# MB1066.net
KiCad netlist of a schematic drawn in Altium Designer
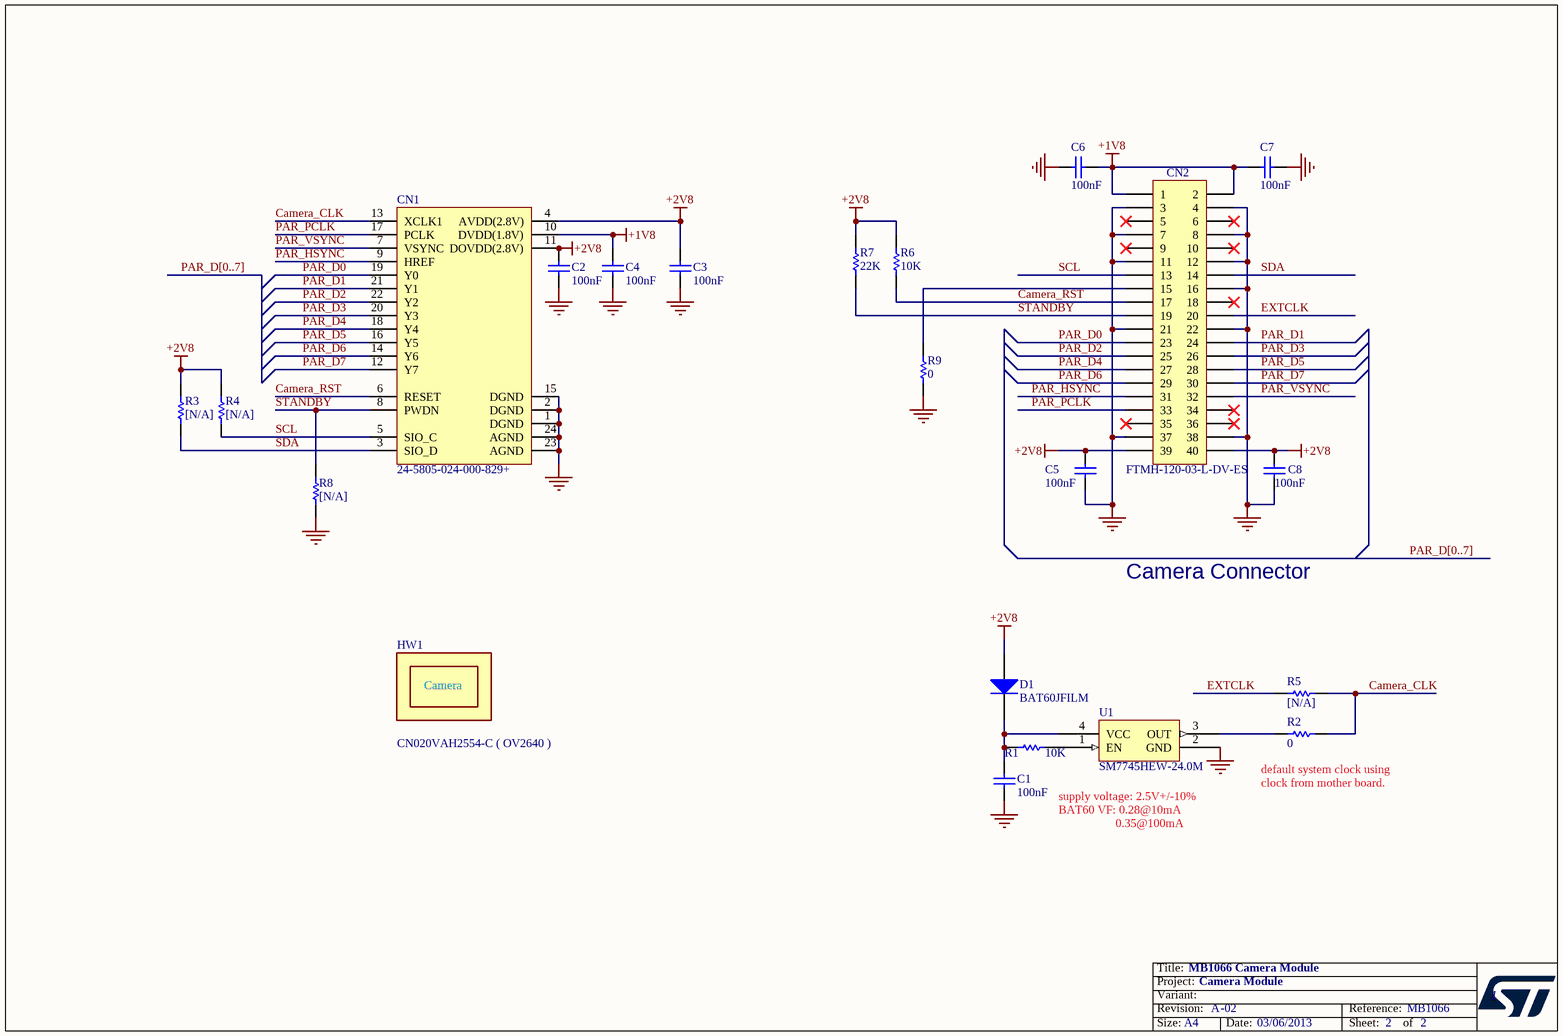
[diagram p0: MB1066.SchDoc]

(export (version "E")
  (design (tool "Eeschema 10.0.6"))
  (components
    (comp (ref "C1")
      (value "100nF")
      (footprint "0603C")
      (description "Capacitor")
      (fields (field (name "PUBLISHER") "Altium Limited"))
      (libsource (lib "Miscellaneous Devices") (part "Cap"))
    )
    (comp (ref "C2")
      (value "100nF")
      (footprint "0603C")
      (description "Capacitor")
      (fields (field (name "PUBLISHER") "Altium Limited"))
      (libsource (lib "Miscellaneous Devices") (part "Cap"))
    )
    (comp (ref "C3")
      (value "100nF")
      (footprint "0603L")
      (description "Capacitor")
      (fields (field (name "PUBLISHER") "Altium Limited"))
      (libsource (lib "Miscellaneous Devices") (part "Cap"))
    )
    (comp (ref "C4")
      (value "100nF")
      (footprint "0603C")
      (description "Capacitor")
      (fields (field (name "PUBLISHER") "Altium Limited"))
      (libsource (lib "Miscellaneous Devices") (part "Cap"))
    )
    (comp (ref "C5")
      (value "100nF")
      (footprint "0603C")
      (description "Capacitor")
      (fields (field (name "PUBLISHER") "Altium Limited"))
      (libsource (lib "Miscellaneous Devices") (part "Cap"))
    )
    (comp (ref "C6")
      (value "100nF")
      (footprint "0603C")
      (description "Capacitor")
      (fields (field (name "PUBLISHER") "Altium Limited"))
      (libsource (lib "Miscellaneous Devices") (part "Cap"))
    )
    (comp (ref "C7")
      (value "100nF")
      (footprint "0603C")
      (description "Capacitor")
      (fields (field (name "PUBLISHER") "Altium Limited"))
      (libsource (lib "Miscellaneous Devices") (part "Cap"))
    )
    (comp (ref "C8")
      (value "100nF")
      (footprint "0603C")
      (description "Capacitor")
      (fields (field (name "PUBLISHER") "Altium Limited"))
      (libsource (lib "Miscellaneous Devices") (part "Cap"))
    )
    (comp (ref "CN1")
      (value "24-5805-024-000-829+")
      (footprint "24-5805-024-000-829")
      (libsource (lib "MB786") (part "24-5805-024-000-829+"))
    )
    (comp (ref "CN2")
      (value "FTMH-120-03-L-DV-ES")
      (footprint "FTMH-120-03-L-DV-ES")
      (description "20*2Pins, 1mm_SMT, male")
      (fields (field (name "PUBLISHER") "Altium Limited"))
      (libsource (lib "Miscellaneous Connectors") (part "Header 20X2"))
    )
    (comp (ref "D1")
      (value "BAT60JFILM")
      (footprint "SOD-323")
      (description "Default Diode")
      (fields (field (name "PUBLISHER") "Altium Limited"))
      (libsource (lib "Miscellaneous Devices") (part "Diode"))
    )
    (comp (ref "HW1") (value "CN020VAH2554-C ( OV2640 )") (libsource (lib "Schlib1") (part "Camera_MODULE")))
    (comp (ref "R1")
      (value "10K")
      (footprint "0603R")
      (description "Resistor")
      (fields (field (name "PUBLISHER") "Altium Limited"))
      (libsource (lib "Miscellaneous Devices") (part "Res1"))
    )
    (comp (ref "R2")
      (value "0")
      (footprint "0603R")
      (description "Resistor")
      (fields (field (name "PUBLISHER") "Altium Limited"))
      (libsource (lib "Miscellaneous Devices") (part "Res1"))
    )
    (comp (ref "R3")
      (value "[N/A]")
      (footprint "0603R")
      (description "Resistor 10K")
      (fields (field (name "PUBLISHER") "Altium Limited"))
      (libsource (lib "Miscellaneous Devices") (part "Res1"))
    )
    (comp (ref "R4")
      (value "[N/A]")
      (footprint "0603R")
      (description "Resistor")
      (fields (field (name "PUBLISHER") "Altium Limited"))
      (libsource (lib "Miscellaneous Devices") (part "Res1"))
    )
    (comp (ref "R5")
      (value "[N/A]")
      (footprint "0603R")
      (description "Resistor")
      (fields (field (name "PUBLISHER") "Altium Limited"))
      (libsource (lib "Miscellaneous Devices") (part "Res1"))
    )
    (comp (ref "R6")
      (value "10K")
      (footprint "0603R")
      (description "Resistor")
      (fields (field (name "PUBLISHER") "Altium Limited"))
      (libsource (lib "Miscellaneous Devices") (part "Res1"))
    )
    (comp (ref "R7")
      (value "22K")
      (footprint "0603R")
      (description "Resistor")
      (fields (field (name "PUBLISHER") "Altium Limited"))
      (libsource (lib "Miscellaneous Devices") (part "Res1"))
    )
    (comp (ref "R8")
      (value "[N/A]")
      (footprint "0603R")
      (description "Resistor")
      (fields (field (name "PUBLISHER") "Altium Limited"))
      (libsource (lib "Miscellaneous Devices") (part "Res1"))
    )
    (comp (ref "R9")
      (value "0")
      (footprint "0603R")
      (description "Resistor")
      (fields (field (name "PUBLISHER") "Altium Limited"))
      (libsource (lib "Miscellaneous Devices") (part "Res1"))
    )
    (comp (ref "U1")
      (value "SM7745HEW-24.0M")
      (footprint "XTAL_5X7")
      (libsource (lib "MB784") (part "SM7745HEV-50.0M"))
    )
  )
  (nets
    (net (code "1") (name "+1V8") (class "Default")
      (node (ref "C4") (pin "1") (pinfunction "1_1") (pintype "passive"))
      (node (ref "C6") (pin "2") (pinfunction "2_2") (pintype "passive"))
      (node (ref "C7") (pin "1") (pinfunction "1_1") (pintype "passive"))
      (node (ref "CN1") (pin "10") (pinfunction "DVDD(1.8V)_10") (pintype "passive"))
      (node (ref "CN2") (pin "1") (pinfunction "1_1") (pintype "passive"))
      (node (ref "CN2") (pin "2") (pinfunction "2_2") (pintype "passive"))
    )
    (net (code "2") (name "+2V8") (class "Default")
      (node (ref "C2") (pin "1") (pinfunction "1_1") (pintype "passive"))
      (node (ref "C3") (pin "1") (pinfunction "1_1") (pintype "passive"))
      (node (ref "C5") (pin "1") (pinfunction "1_1") (pintype "passive"))
      (node (ref "C8") (pin "1") (pinfunction "1_1") (pintype "passive"))
      (node (ref "CN1") (pin "11") (pinfunction "DOVDD(2.8V)_11") (pintype "passive"))
      (node (ref "CN1") (pin "4") (pinfunction "AVDD(2.8V)_4") (pintype "passive"))
      (node (ref "CN2") (pin "39") (pinfunction "39_39") (pintype "passive"))
      (node (ref "CN2") (pin "40") (pinfunction "40_40") (pintype "passive"))
      (node (ref "D1") (pin "1") (pinfunction "A_1") (pintype "passive"))
      (node (ref "R3") (pin "1") (pinfunction "1_1") (pintype "passive"))
      (node (ref "R4") (pin "1") (pinfunction "1_1") (pintype "passive"))
      (node (ref "R6") (pin "1") (pinfunction "1_1") (pintype "passive"))
      (node (ref "R7") (pin "1") (pinfunction "1_1") (pintype "passive"))
    )
    (net (code "3") (name "/Camera_CLK") (class "Default")
      (node (ref "CN1") (pin "13") (pinfunction "XCLK1_13") (pintype "passive"))
      (node (ref "R2") (pin "2") (pinfunction "2_2") (pintype "passive"))
      (node (ref "R5") (pin "2") (pinfunction "2_2") (pintype "passive"))
    )
    (net (code "4") (name "/Camera_RST") (class "Default")
      (node (ref "CN1") (pin "6") (pinfunction "RESET_6") (pintype "passive"))
      (node (ref "CN2") (pin "17") (pinfunction "17_17") (pintype "passive"))
      (node (ref "R6") (pin "2") (pinfunction "2_2") (pintype "passive"))
    )
    (net (code "5") (name "/EXTCLK") (class "Default")
      (node (ref "CN2") (pin "20") (pinfunction "20_20") (pintype "passive"))
      (node (ref "R5") (pin "1") (pinfunction "1_1") (pintype "passive"))
    )
    (net (code "6") (name "/PAR_D0") (class "Default")
      (node (ref "CN1") (pin "19") (pinfunction "Y0_19") (pintype "passive"))
      (node (ref "CN2") (pin "23") (pinfunction "23_23") (pintype "passive"))
    )
    (net (code "7") (name "/PAR_D1") (class "Default")
      (node (ref "CN1") (pin "21") (pinfunction "Y1_21") (pintype "passive"))
      (node (ref "CN2") (pin "24") (pinfunction "24_24") (pintype "passive"))
    )
    (net (code "8") (name "/PAR_D2") (class "Default")
      (node (ref "CN1") (pin "22") (pinfunction "Y2_22") (pintype "passive"))
      (node (ref "CN2") (pin "25") (pinfunction "25_25") (pintype "passive"))
    )
    (net (code "9") (name "/PAR_D3") (class "Default")
      (node (ref "CN1") (pin "20") (pinfunction "Y3_20") (pintype "passive"))
      (node (ref "CN2") (pin "26") (pinfunction "26_26") (pintype "passive"))
    )
    (net (code "10") (name "/PAR_D4") (class "Default")
      (node (ref "CN1") (pin "18") (pinfunction "Y4_18") (pintype "passive"))
      (node (ref "CN2") (pin "27") (pinfunction "27_27") (pintype "passive"))
    )
    (net (code "11") (name "/PAR_D5") (class "Default")
      (node (ref "CN1") (pin "16") (pinfunction "Y5_16") (pintype "passive"))
      (node (ref "CN2") (pin "28") (pinfunction "28_28") (pintype "passive"))
    )
    (net (code "12") (name "/PAR_D6") (class "Default")
      (node (ref "CN1") (pin "14") (pinfunction "Y6_14") (pintype "passive"))
      (node (ref "CN2") (pin "29") (pinfunction "29_29") (pintype "passive"))
    )
    (net (code "13") (name "/PAR_D7") (class "Default")
      (node (ref "CN1") (pin "12") (pinfunction "Y7_12") (pintype "passive"))
      (node (ref "CN2") (pin "30") (pinfunction "30_30") (pintype "passive"))
    )
    (net (code "15") (name "/PAR_HSYNC") (class "Default")
      (node (ref "CN1") (pin "9") (pinfunction "HREF_9") (pintype "passive"))
      (node (ref "CN2") (pin "31") (pinfunction "31_31") (pintype "passive"))
    )
    (net (code "16") (name "/PAR_PCLK") (class "Default")
      (node (ref "CN1") (pin "17") (pinfunction "PCLK_17") (pintype "passive"))
      (node (ref "CN2") (pin "33") (pinfunction "33_33") (pintype "passive"))
    )
    (net (code "17") (name "/PAR_VSYNC") (class "Default")
      (node (ref "CN1") (pin "7") (pinfunction "VSYNC_7") (pintype "passive"))
      (node (ref "CN2") (pin "32") (pinfunction "32_32") (pintype "passive"))
    )
    (net (code "18") (name "/SCL") (class "Default")
      (node (ref "CN1") (pin "5") (pinfunction "SIO_C_5") (pintype "passive"))
      (node (ref "CN2") (pin "13") (pinfunction "13_13") (pintype "passive"))
      (node (ref "R4") (pin "2") (pinfunction "2_2") (pintype "passive"))
    )
    (net (code "19") (name "/SDA") (class "Default")
      (node (ref "CN1") (pin "3") (pinfunction "SIO_D_3") (pintype "passive"))
      (node (ref "CN2") (pin "14") (pinfunction "14_14") (pintype "passive"))
      (node (ref "R3") (pin "2") (pinfunction "2_2") (pintype "passive"))
    )
    (net (code "20") (name "/STANDBY") (class "Default")
      (node (ref "CN1") (pin "8") (pinfunction "PWDN_8") (pintype "passive"))
      (node (ref "CN2") (pin "19") (pinfunction "19_19") (pintype "passive"))
      (node (ref "R7") (pin "2") (pinfunction "2_2") (pintype "passive"))
      (node (ref "R8") (pin "2") (pinfunction "2_2") (pintype "passive"))
    )
    (net (code "21") (name "GND") (class "Default")
      (node (ref "C1") (pin "2") (pinfunction "2_2") (pintype "passive"))
      (node (ref "C2") (pin "2") (pinfunction "2_2") (pintype "passive"))
      (node (ref "C3") (pin "2") (pinfunction "2_2") (pintype "passive"))
      (node (ref "C4") (pin "2") (pinfunction "2_2") (pintype "passive"))
      (node (ref "C5") (pin "2") (pinfunction "2_2") (pintype "passive"))
      (node (ref "C6") (pin "1") (pinfunction "1_1") (pintype "passive"))
      (node (ref "C7") (pin "2") (pinfunction "2_2") (pintype "passive"))
      (node (ref "C8") (pin "2") (pinfunction "2_2") (pintype "passive"))
      (node (ref "CN1") (pin "1") (pinfunction "DGND_1") (pintype "passive"))
      (node (ref "CN1") (pin "15") (pinfunction "DGND_15") (pintype "passive"))
      (node (ref "CN1") (pin "2") (pinfunction "DGND_2") (pintype "passive"))
      (node (ref "CN1") (pin "23") (pinfunction "AGND_23") (pintype "passive"))
      (node (ref "CN1") (pin "24") (pinfunction "AGND_24") (pintype "passive"))
      (node (ref "CN2") (pin "11") (pinfunction "11_11") (pintype "passive"))
      (node (ref "CN2") (pin "12") (pinfunction "12_12") (pintype "passive"))
      (node (ref "CN2") (pin "16") (pinfunction "16_16") (pintype "passive"))
      (node (ref "CN2") (pin "21") (pinfunction "21_21") (pintype "passive"))
      (node (ref "CN2") (pin "22") (pinfunction "22_22") (pintype "passive"))
      (node (ref "CN2") (pin "3") (pinfunction "3_3") (pintype "passive"))
      (node (ref "CN2") (pin "37") (pinfunction "37_37") (pintype "passive"))
      (node (ref "CN2") (pin "38") (pinfunction "38_38") (pintype "passive"))
      (node (ref "CN2") (pin "4") (pinfunction "4_4") (pintype "passive"))
      (node (ref "CN2") (pin "7") (pinfunction "7_7") (pintype "passive"))
      (node (ref "CN2") (pin "8") (pinfunction "8_8") (pintype "passive"))
      (node (ref "R8") (pin "1") (pinfunction "1_1") (pintype "passive"))
      (node (ref "R9") (pin "2") (pinfunction "2_2") (pintype "passive"))
      (node (ref "U1") (pin "2") (pinfunction "GND_2") (pintype "passive"))
    )
    (net (code "22") (name "Net-(CN2-Pad15)") (class "Default")
      (node (ref "CN2") (pin "15") (pinfunction "15_15") (pintype "passive"))
      (node (ref "R9") (pin "1") (pinfunction "1_1") (pintype "passive"))
    )
    (net (code "23") (name "Net-(D1-K)") (class "Default")
      (node (ref "C1") (pin "1") (pinfunction "1_1") (pintype "passive"))
      (node (ref "D1") (pin "2") (pinfunction "K_2") (pintype "passive"))
      (node (ref "R1") (pin "1") (pinfunction "1_1") (pintype "passive"))
      (node (ref "U1") (pin "4") (pinfunction "VCC_4") (pintype "passive"))
    )
    (net (code "24") (name "Net-(U1-EN)") (class "Default")
      (node (ref "R1") (pin "2") (pinfunction "2_2") (pintype "passive"))
      (node (ref "U1") (pin "1") (pinfunction "EN_1") (pintype "input"))
    )
    (net (code "25") (name "Net-(U1-OUT)") (class "Default")
      (node (ref "R2") (pin "1") (pinfunction "1_1") (pintype "passive"))
      (node (ref "U1") (pin "3") (pinfunction "OUT_3") (pintype "output"))
    )
    (net (code "26") (name "unconnected-(CN2-Pad5)") (class "Default")
      (node (ref "CN2") (pin "5") (pinfunction "5_5") (pintype "passive+no_connect"))
    )
    (net (code "27") (name "unconnected-(CN2-Pad6)") (class "Default")
      (node (ref "CN2") (pin "6") (pinfunction "6_6") (pintype "passive+no_connect"))
    )
    (net (code "28") (name "unconnected-(CN2-Pad9)") (class "Default")
      (node (ref "CN2") (pin "9") (pinfunction "9_9") (pintype "passive+no_connect"))
    )
    (net (code "29") (name "unconnected-(CN2-Pad10)") (class "Default")
      (node (ref "CN2") (pin "10") (pinfunction "10_10") (pintype "passive+no_connect"))
    )
    (net (code "30") (name "unconnected-(CN2-Pad18)") (class "Default")
      (node (ref "CN2") (pin "18") (pinfunction "18_18") (pintype "passive+no_connect"))
    )
    (net (code "31") (name "unconnected-(CN2-Pad34)") (class "Default")
      (node (ref "CN2") (pin "34") (pinfunction "34_34") (pintype "passive+no_connect"))
    )
    (net (code "32") (name "unconnected-(CN2-Pad35)") (class "Default")
      (node (ref "CN2") (pin "35") (pinfunction "35_35") (pintype "passive+no_connect"))
    )
    (net (code "33") (name "unconnected-(CN2-Pad36)") (class "Default")
      (node (ref "CN2") (pin "36") (pinfunction "36_36") (pintype "passive+no_connect"))
    )
  )
)
